# DIGISPARK_PRODUCTION_REV3.net
KiCad netlist of a schematic drawn in EAGLE
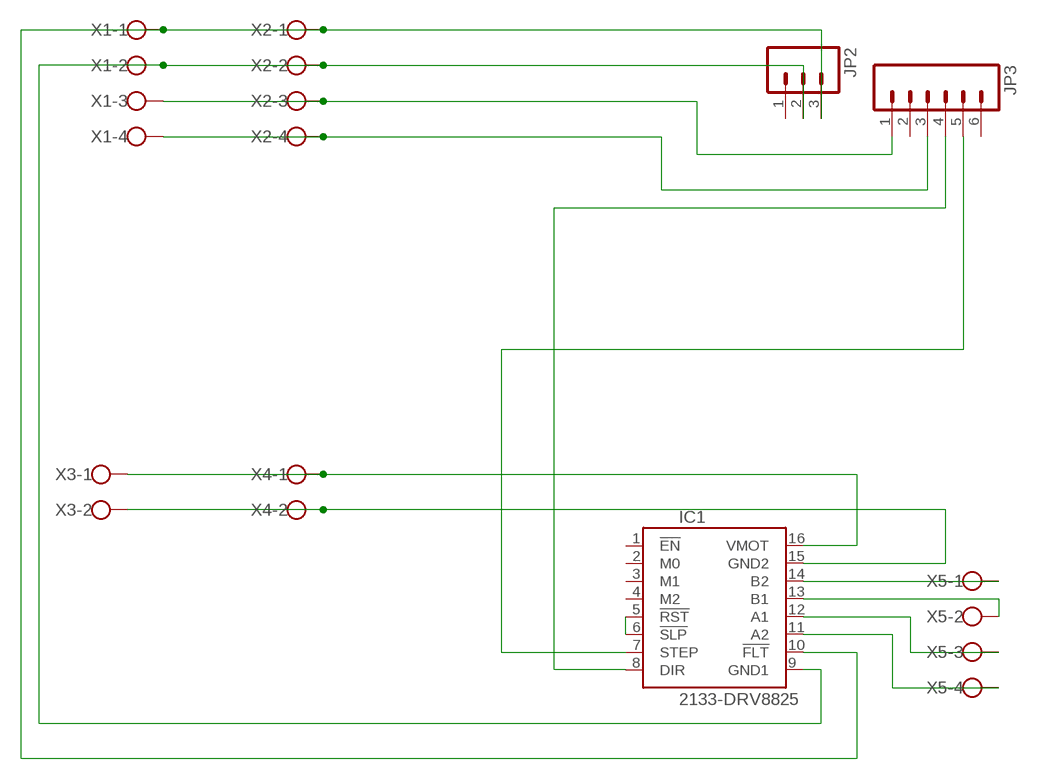
[diagram p0: schematic, sheet 1]

(export (version "E")
  (design (tool "Eeschema 10.0.6"))
  (components
    (comp (ref "IC1")
      (value "2133-DRV8825")
      (footprint "eagle-import:DRV8825")
      (libsource (lib "eagle-import") (part "2133-DRV8825"))
    )
    (comp (ref "JP2")
      (value "M03PTH")
      (footprint "eagle-import:1X03")
      (libsource (lib "eagle-import") (part "M03PTH"))
    )
    (comp (ref "JP3")
      (value "M06SIP")
      (footprint "eagle-import:1X06")
      (libsource (lib "eagle-import") (part "M06SIP"))
    )
    (comp (ref "X1")
      (value "W237-4")
      (footprint "eagle-import:W237-4")
      (libsource (lib "eagle-import") (part "W237-4"))
    )
    (comp (ref "X2")
      (value "W237-4")
      (footprint "eagle-import:W237-4")
      (libsource (lib "eagle-import") (part "W237-4"))
    )
    (comp (ref "X3")
      (value "W237-102")
      (footprint "eagle-import:W237-102")
      (fields (field (name "MPN") "237-102"))
      (libsource (lib "eagle-import") (part "W237-102"))
    )
    (comp (ref "X4")
      (value "W237-102")
      (footprint "eagle-import:W237-102")
      (fields (field (name "MPN") "237-102"))
      (libsource (lib "eagle-import") (part "W237-102"))
    )
    (comp (ref "X5")
      (value "W237-4")
      (footprint "eagle-import:W237-4")
      (libsource (lib "eagle-import") (part "W237-4"))
    )
  )
  (nets
    (net (code "1") (name "Net-(IC1-A1)") (class "Default")
      (node (ref "IC1") (pin "12") (pinfunction "A1_12") (pintype "output"))
      (node (ref "X5") (pin "3") (pinfunction "KL_3") (pintype "passive"))
    )
    (net (code "2") (name "Net-(IC1-A2)") (class "Default")
      (node (ref "IC1") (pin "11") (pinfunction "A2_11") (pintype "output"))
      (node (ref "X5") (pin "4") (pinfunction "KL_4") (pintype "passive"))
    )
    (net (code "3") (name "Net-(IC1-B1)") (class "Default")
      (node (ref "IC1") (pin "13") (pinfunction "B1_13") (pintype "output"))
      (node (ref "X5") (pin "2") (pinfunction "KL_2") (pintype "passive"))
    )
    (net (code "4") (name "Net-(IC1-B2)") (class "Default")
      (node (ref "IC1") (pin "14") (pinfunction "B2_14") (pintype "output"))
      (node (ref "X5") (pin "1") (pinfunction "KL_1") (pintype "passive"))
    )
    (net (code "5") (name "Net-(IC1-DIR)") (class "Default")
      (node (ref "IC1") (pin "8") (pinfunction "DIR_8") (pintype "input"))
      (node (ref "JP3") (pin "4") (pinfunction "4_4") (pintype "passive"))
    )
    (net (code "6") (name "Net-(IC1-GND1)") (class "Default")
      (node (ref "IC1") (pin "9") (pinfunction "GND1_9") (pintype "power_in"))
      (node (ref "JP2") (pin "2") (pinfunction "2_2") (pintype "passive"))
      (node (ref "X1") (pin "2") (pinfunction "KL_2") (pintype "passive"))
      (node (ref "X2") (pin "2") (pinfunction "KL_2") (pintype "passive"))
    )
    (net (code "7") (name "Net-(IC1-GND2)") (class "Default")
      (node (ref "IC1") (pin "15") (pinfunction "GND2_15") (pintype "power_in"))
      (node (ref "X3") (pin "2") (pinfunction "KL_2") (pintype "passive"))
      (node (ref "X4") (pin "2") (pinfunction "KL_2") (pintype "passive"))
    )
    (net (code "8") (name "Net-(IC1-STEP)") (class "Default")
      (node (ref "IC1") (pin "7") (pinfunction "STEP_7") (pintype "input"))
      (node (ref "JP3") (pin "5") (pinfunction "5_5") (pintype "passive"))
    )
    (net (code "9") (name "Net-(IC1-VMOT)") (class "Default")
      (node (ref "IC1") (pin "16") (pinfunction "VMOT_16") (pintype "power_in"))
      (node (ref "X3") (pin "1") (pinfunction "KL_1") (pintype "passive"))
      (node (ref "X4") (pin "1") (pinfunction "KL_1") (pintype "passive"))
    )
    (net (code "10") (name "Net-(IC1-~{FLT})") (class "Default")
      (node (ref "IC1") (pin "10") (pinfunction "~{FLT}_10") (pintype "open_collector"))
      (node (ref "JP2") (pin "3") (pinfunction "3_3") (pintype "passive"))
      (node (ref "X1") (pin "1") (pinfunction "KL_1") (pintype "passive"))
      (node (ref "X2") (pin "1") (pinfunction "KL_1") (pintype "passive"))
    )
    (net (code "11") (name "Net-(IC1-~{RST})") (class "Default")
      (node (ref "IC1") (pin "5") (pinfunction "~{RST}_5") (pintype "input"))
      (node (ref "IC1") (pin "6") (pinfunction "~{SLP}_6") (pintype "input"))
    )
    (net (code "12") (name "Net-(X1C-KL)") (class "Default")
      (node (ref "JP3") (pin "1") (pinfunction "1_1") (pintype "passive"))
      (node (ref "X1") (pin "3") (pinfunction "KL_3") (pintype "passive"))
      (node (ref "X2") (pin "3") (pinfunction "KL_3") (pintype "passive"))
    )
    (net (code "13") (name "Net-(X1D-KL)") (class "Default")
      (node (ref "JP3") (pin "3") (pinfunction "3_3") (pintype "passive"))
      (node (ref "X1") (pin "4") (pinfunction "KL_4") (pintype "passive"))
      (node (ref "X2") (pin "4") (pinfunction "KL_4") (pintype "passive"))
    )
    (net (code "14") (name "unconnected-(IC1-M0-Pad2)") (class "Default")
      (node (ref "IC1") (pin "2") (pinfunction "M0_2") (pintype "passive"))
    )
    (net (code "15") (name "unconnected-(IC1-M1-Pad3)") (class "Default")
      (node (ref "IC1") (pin "3") (pinfunction "M1_3") (pintype "passive"))
    )
    (net (code "16") (name "unconnected-(IC1-M2-Pad4)") (class "Default")
      (node (ref "IC1") (pin "4") (pinfunction "M2_4") (pintype "passive"))
    )
    (net (code "17") (name "unconnected-(IC1-~{EN}-Pad1)") (class "Default")
      (node (ref "IC1") (pin "1") (pinfunction "~{EN}_1") (pintype "passive"))
    )
    (net (code "18") (name "unconnected-(JP2-Pad1)") (class "Default")
      (node (ref "JP2") (pin "1") (pinfunction "1_1") (pintype "passive"))
    )
    (net (code "19") (name "unconnected-(JP3-Pad2)") (class "Default")
      (node (ref "JP3") (pin "2") (pinfunction "2_2") (pintype "passive"))
    )
    (net (code "20") (name "unconnected-(JP3-Pad6)") (class "Default")
      (node (ref "JP3") (pin "6") (pinfunction "6_6") (pintype "passive"))
    )
  )
)
